# 250.net
KiCad netlist of a schematic drawn in EAGLE
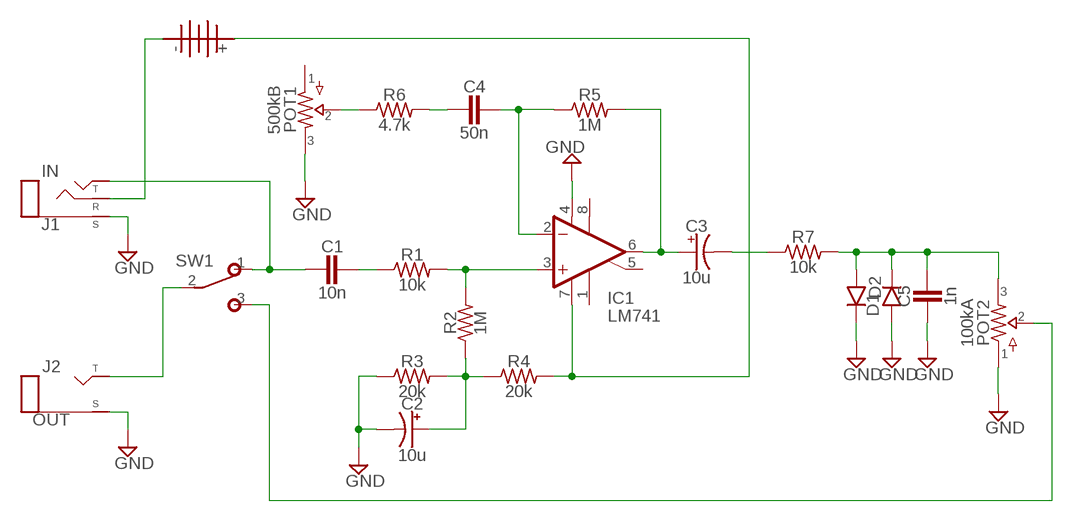
[diagram p0: schematic, sheet 1]

(export (version "E")
  (design (tool "Eeschema 10.0.6"))
  (components
    (comp (ref "1")
      (value "9V")
      (footprint "eagle-import:TWO_PADS")
      (libsource (lib "eagle-import") (part "BATTERY"))
    )
    (comp (ref "C1")
      (value "10n")
      (footprint "eagle-import:BOX_SMALL")
      (libsource (lib "eagle-import") (part "CER/FILMBOX.1"))
    )
    (comp (ref "C2")
      (value "10u")
      (footprint "eagle-import:050_020")
      (libsource (lib "eagle-import") (part "0500"))
    )
    (comp (ref "C3")
      (value "10u")
      (footprint "eagle-import:050_020")
      (libsource (lib "eagle-import") (part "0500"))
    )
    (comp (ref "C4")
      (value "50n")
      (footprint "eagle-import:BOX_SMALL")
      (libsource (lib "eagle-import") (part "CER/FILMBOX.1"))
    )
    (comp (ref "C5")
      (value "1n")
      (footprint "eagle-import:BOX_SMALL")
      (libsource (lib "eagle-import") (part "CER/FILMBOX.1"))
    )
    (comp (ref "D1")
      (value "DO35.2")
      (footprint "eagle-import:DO35-2")
      (libsource (lib "eagle-import") (part "DO35.2"))
    )
    (comp (ref "D2")
      (value "DO35.2")
      (footprint "eagle-import:DO35-2")
      (libsource (lib "eagle-import") (part "DO35.2"))
    )
    (comp (ref "IC1")
      (value "LM741")
      (footprint "eagle-import:DIL0")
      (libsource (lib "eagle-import") (part "SINGLETH"))
    )
    (comp (ref "J1")
      (value "IN")
      (footprint "eagle-import:STEREO_PCB")
      (libsource (lib "eagle-import") (part "STEREO"))
    )
    (comp (ref "J2")
      (value "OUT")
      (footprint "eagle-import:MONO_SW")
      (libsource (lib "eagle-import") (part "MONO_JACK"))
    )
    (comp (ref "POT1")
      (value "500kB")
      (footprint "eagle-import:16MM")
      (libsource (lib "eagle-import") (part "POTS16MM"))
    )
    (comp (ref "POT2")
      (value "100kA")
      (footprint "eagle-import:16MM")
      (libsource (lib "eagle-import") (part "POTS16MM"))
    )
    (comp (ref "R1")
      (value "10k")
      (footprint "eagle-import:R0207_3")
      (libsource (lib "eagle-import") (part "R_.3B"))
    )
    (comp (ref "R2")
      (value "1M")
      (footprint "eagle-import:R0207_3")
      (libsource (lib "eagle-import") (part "R_.3B"))
    )
    (comp (ref "R3")
      (value "20k")
      (footprint "eagle-import:R0207_3")
      (libsource (lib "eagle-import") (part "R_.3B"))
    )
    (comp (ref "R4")
      (value "20k")
      (footprint "eagle-import:R0207_3")
      (libsource (lib "eagle-import") (part "R_.3B"))
    )
    (comp (ref "R5")
      (value "1M")
      (footprint "eagle-import:R0207_3")
      (libsource (lib "eagle-import") (part "R_.3B"))
    )
    (comp (ref "R6")
      (value "4.7k")
      (footprint "eagle-import:R0207_3")
      (libsource (lib "eagle-import") (part "R_.3B"))
    )
    (comp (ref "R7")
      (value "10k")
      (footprint "eagle-import:R0207_3")
      (libsource (lib "eagle-import") (part "R_.3B"))
    )
    (comp (ref "SW1")
      (value "SPDT")
      (footprint "eagle-import:M9040P")
      (libsource (lib "eagle-import") (part "SPDT"))
    )
  )
  (nets
    (net (code "1") (name "GND") (class "Default")
      (node (ref "C2") (pin "-") (pinfunction "-_-") (pintype "passive"))
      (node (ref "C5") (pin "2") (pinfunction "2_2") (pintype "passive"))
      (node (ref "D1") (pin "C") (pinfunction "C_C") (pintype "passive"))
      (node (ref "D2") (pin "A") (pinfunction "A_A") (pintype "passive"))
      (node (ref "IC1") (pin "4") (pinfunction "V-_4") (pintype "power_in"))
      (node (ref "J1") (pin "P$1") (pinfunction "S_P$1") (pintype "passive"))
      (node (ref "J2") (pin "S") (pinfunction "SLEEVE_S") (pintype "passive"))
      (node (ref "POT1") (pin "3") (pinfunction "3_3") (pintype "passive"))
      (node (ref "POT2") (pin "1") (pinfunction "1_1") (pintype "passive"))
      (node (ref "R3") (pin "1") (pinfunction "1_1") (pintype "passive"))
    )
    (net (code "2") (name "Net-(1-P$1)") (class "Default")
      (node (ref "1") (pin "T") (pinfunction "P$1_T") (pintype "bidirectional"))
      (node (ref "IC1") (pin "7") (pinfunction "V+_7") (pintype "power_in"))
      (node (ref "R4") (pin "2") (pinfunction "2_2") (pintype "passive"))
    )
    (net (code "3") (name "Net-(1-P$2)") (class "Default")
      (node (ref "1") (pin "S") (pinfunction "P$2_S") (pintype "bidirectional"))
      (node (ref "J1") (pin "P$2") (pinfunction "R_P$2") (pintype "passive"))
    )
    (net (code "4") (name "Net-(C1-Pad1)") (class "Default")
      (node (ref "C1") (pin "1") (pinfunction "1_1") (pintype "passive"))
      (node (ref "R1") (pin "1") (pinfunction "1_1") (pintype "passive"))
    )
    (net (code "5") (name "Net-(C2-Pad+)") (class "Default")
      (node (ref "C2") (pin "+") (pinfunction "+_+") (pintype "passive"))
      (node (ref "R2") (pin "1") (pinfunction "1_1") (pintype "passive"))
      (node (ref "R3") (pin "2") (pinfunction "2_2") (pintype "passive"))
      (node (ref "R4") (pin "1") (pinfunction "1_1") (pintype "passive"))
    )
    (net (code "6") (name "Net-(C3-Pad-)") (class "Default")
      (node (ref "C3") (pin "-") (pinfunction "-_-") (pintype "passive"))
      (node (ref "R7") (pin "1") (pinfunction "1_1") (pintype "passive"))
    )
    (net (code "7") (name "Net-(C4-Pad2)") (class "Default")
      (node (ref "C4") (pin "2") (pinfunction "2_2") (pintype "passive"))
      (node (ref "R6") (pin "2") (pinfunction "2_2") (pintype "passive"))
    )
    (net (code "8") (name "Net-(C5-Pad1)") (class "Default")
      (node (ref "C5") (pin "1") (pinfunction "1_1") (pintype "passive"))
      (node (ref "D1") (pin "A") (pinfunction "A_A") (pintype "passive"))
      (node (ref "D2") (pin "C") (pinfunction "C_C") (pintype "passive"))
      (node (ref "POT2") (pin "3") (pinfunction "3_3") (pintype "passive"))
      (node (ref "R7") (pin "2") (pinfunction "2_2") (pintype "passive"))
    )
    (net (code "9") (name "Net-(IC1-+IN)") (class "Default")
      (node (ref "IC1") (pin "3") (pinfunction "+IN_3") (pintype "input"))
      (node (ref "R1") (pin "2") (pinfunction "2_2") (pintype "passive"))
      (node (ref "R2") (pin "2") (pinfunction "2_2") (pintype "passive"))
    )
    (net (code "10") (name "Net-(IC1--IN)") (class "Default")
      (node (ref "C4") (pin "1") (pinfunction "1_1") (pintype "passive"))
      (node (ref "IC1") (pin "2") (pinfunction "-IN_2") (pintype "input"))
      (node (ref "R5") (pin "1") (pinfunction "1_1") (pintype "passive"))
    )
    (net (code "11") (name "Net-(IC1-OUT)") (class "Default")
      (node (ref "C3") (pin "+") (pinfunction "+_+") (pintype "passive"))
      (node (ref "IC1") (pin "6") (pinfunction "OUT_6") (pintype "output"))
      (node (ref "R5") (pin "2") (pinfunction "2_2") (pintype "passive"))
    )
    (net (code "12") (name "Net-(J1-T)") (class "Default")
      (node (ref "C1") (pin "2") (pinfunction "2_2") (pintype "passive"))
      (node (ref "J1") (pin "P$3") (pinfunction "T_P$3") (pintype "passive"))
      (node (ref "SW1") (pin "1") (pinfunction "O_1") (pintype "passive"))
    )
    (net (code "13") (name "Net-(J2-TIP)") (class "Default")
      (node (ref "J2") (pin "T") (pinfunction "TIP_T") (pintype "passive"))
      (node (ref "SW1") (pin "2") (pinfunction "P_2") (pintype "passive"))
    )
    (net (code "14") (name "Net-(POT1-Pad2)") (class "Default")
      (node (ref "POT1") (pin "2") (pinfunction "2_2") (pintype "passive"))
      (node (ref "R6") (pin "1") (pinfunction "1_1") (pintype "passive"))
    )
    (net (code "15") (name "Net-(SW1-S)") (class "Default")
      (node (ref "POT2") (pin "2") (pinfunction "2_2") (pintype "passive"))
      (node (ref "SW1") (pin "3") (pinfunction "S_3") (pintype "passive"))
    )
    (net (code "16") (name "unconnected-(IC1-ON1-Pad1)") (class "Default")
      (node (ref "IC1") (pin "1") (pinfunction "ON1_1") (pintype "passive"))
    )
    (net (code "17") (name "unconnected-(IC1-ON2-Pad5)") (class "Default")
      (node (ref "IC1") (pin "5") (pinfunction "ON2_5") (pintype "passive"))
    )
    (net (code "18") (name "unconnected-(IC1-OPT-Pad8)") (class "Default")
      (node (ref "IC1") (pin "8") (pinfunction "OPT_8") (pintype "passive"))
    )
    (net (code "19") (name "unconnected-(POT1-Pad1)") (class "Default")
      (node (ref "POT1") (pin "1") (pinfunction "1_1") (pintype "passive"))
    )
  )
)
